# PCB-Main.net
KiCad netlist of a schematic drawn in EAGLE
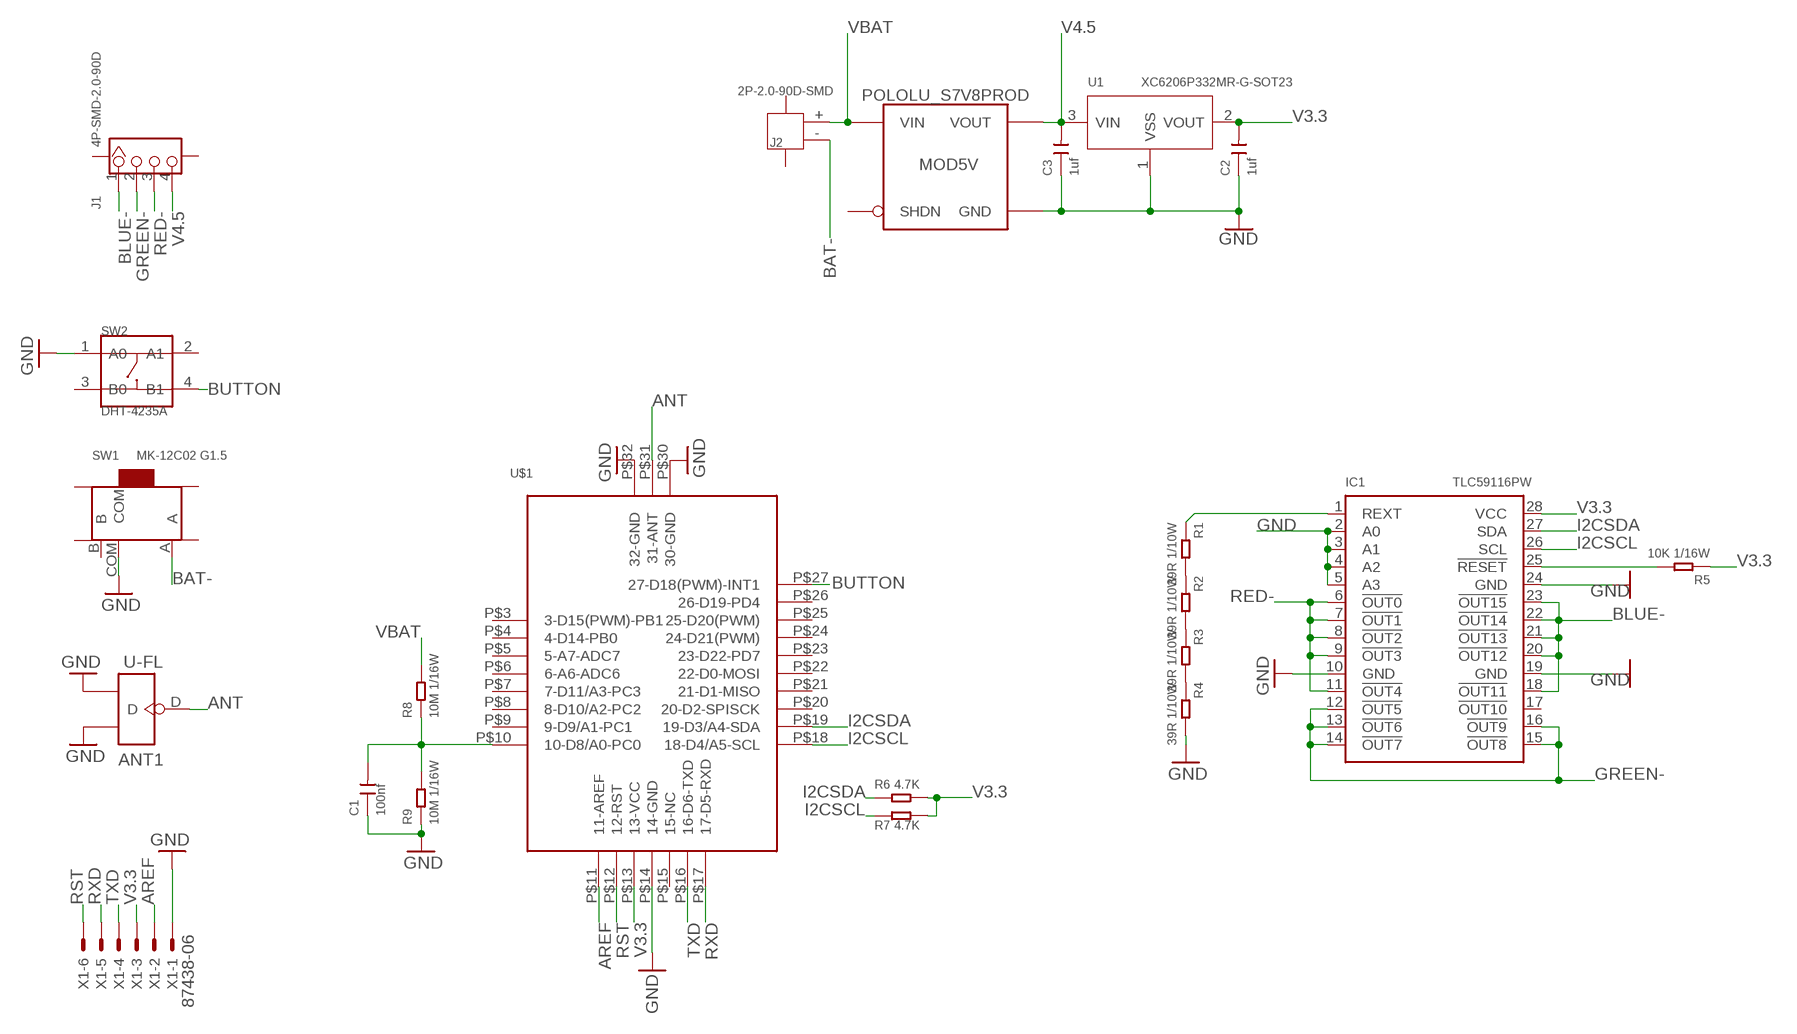
[diagram p0: schematic, sheet 1]

(export (version "E")
  (design (tool "Eeschema 10.0.6"))
  (components
    (comp (ref "ANT1")
      (value "U-FL")
      (footprint "eagle-import:U-FL3P-SMD-2.6X2.6X1.0MM")
      (libsource (lib "eagle-import") (part "ANTENNA-CONN-U-FL(3P)"))
    )
    (comp (ref "C1")
      (value "100nf")
      (footprint "eagle-import:C0402")
      (fields (field (name "MPN") "CC0402KRX7R8BB104"))
      (libsource (lib "eagle-import") (part "CERAMIC-100NF-25V-10%-X7R(0402)"))
    )
    (comp (ref "C2")
      (value "1uf")
      (footprint "eagle-import:C0402")
      (fields (field (name "MPN") "CC0402KRX5R6BB105"))
      (libsource (lib "eagle-import") (part "CERAMIC-1UF-10V-10%-X5R(0402)"))
    )
    (comp (ref "C3")
      (value "1uf")
      (footprint "eagle-import:C0402")
      (fields (field (name "MPN") "CC0402KRX5R6BB105"))
      (libsource (lib "eagle-import") (part "CERAMIC-1UF-10V-10%-X5R(0402)"))
    )
    (comp (ref "IC1")
      (value "TLC59116PW")
      (footprint "eagle-import:PW_R-PDSO-G28")
      (libsource (lib "eagle-import") (part "TLC59116PW"))
    )
    (comp (ref "J1")
      (value "4P-SMD-2.0-90D")
      (footprint "eagle-import:HW4-SMD-2.0-90D")
      (libsource (lib "eagle-import") (part "GROVE-CONNECTOR-SMD-90D(4+2P-2.0)"))
    )
    (comp (ref "J2")
      (value "2P-2.0-90D-SMD")
      (footprint "eagle-import:HW2-SMD-2.0-90D")
      (libsource (lib "eagle-import") (part "CONN-HEADER-SMD-PH-SIDE-(2P-2.0MM)"))
    )
    (comp (ref "MOD5V")
      (value "POLOLU_S7V8PROD")
      (footprint "eagle-import:POLOLU_4P_SIGO")
      (libsource (lib "eagle-import") (part "POLOLU_S7V8PROD"))
    )
    (comp (ref "R1")
      (value "39R 1/10W")
      (footprint "eagle-import:R0603")
      (fields (field (name "MPN") "RC0603JR-0739RL"))
      (libsource (lib "eagle-import") (part "SMD-RES-39R-5%-1/10W(0603)"))
    )
    (comp (ref "R2")
      (value "39R 1/10W")
      (footprint "eagle-import:R0603")
      (fields (field (name "MPN") "RC0603JR-0739RL"))
      (libsource (lib "eagle-import") (part "SMD-RES-39R-5%-1/10W(0603)"))
    )
    (comp (ref "R3")
      (value "39R 1/10W")
      (footprint "eagle-import:R0603")
      (fields (field (name "MPN") "RC0603JR-0739RL"))
      (libsource (lib "eagle-import") (part "SMD-RES-39R-5%-1/10W(0603)"))
    )
    (comp (ref "R4")
      (value "39R 1/10W")
      (footprint "eagle-import:R0603")
      (fields (field (name "MPN") "RC0603JR-0739RL"))
      (libsource (lib "eagle-import") (part "SMD-RES-39R-5%-1/10W(0603)"))
    )
    (comp (ref "R5")
      (value "10K 1/16W")
      (footprint "eagle-import:R0402")
      (fields (field (name "MPN") "RC0402FR-0710KL"))
      (libsource (lib "eagle-import") (part "SMD-RES-10K-1%-1/16W(0402)"))
    )
    (comp (ref "R6")
      (value "4.7K")
      (footprint "eagle-import:R0402")
      (fields (field (name "MPN") "RC0402JR-074K7L"))
      (libsource (lib "eagle-import") (part "SMD-RES-4.7K-5%-1/16W(0402)"))
    )
    (comp (ref "R7")
      (value "4.7K")
      (footprint "eagle-import:R0402")
      (fields (field (name "MPN") "RC0402JR-074K7L"))
      (libsource (lib "eagle-import") (part "SMD-RES-4.7K-5%-1/16W(0402)"))
    )
    (comp (ref "R8")
      (value "10M 1/16W")
      (footprint "eagle-import:R0402")
      (fields (field (name "MPN") "RC0402FR-0710ML"))
      (libsource (lib "eagle-import") (part "SMD-RES-10M-1%-1/16W(0402)"))
    )
    (comp (ref "R9")
      (value "10M 1/16W")
      (footprint "eagle-import:R0402")
      (fields (field (name "MPN") "RC0402FR-0710ML"))
      (libsource (lib "eagle-import") (part "SMD-RES-10M-1%-1/16W(0402)"))
    )
    (comp (ref "SW1")
      (value "MK-12C02 G1.5")
      (footprint "eagle-import:SW7-SMD-L6.7X2.7X3.2MM")
      (libsource (lib "eagle-import") (part "SMD-TOGGLE-SWITCH-ON-ON(3+4P-6.7X2.7MM)"))
    )
    (comp (ref "SW2")
      (value "DHT-4235A")
      (footprint "eagle-import:SW4-SMD-4.2X3.2X2.5MM")
      (libsource (lib "eagle-import") (part "SMD-BUTTON-TOP-DHT-4235A(4P-4.2X3.2MM)"))
    )
    (comp (ref "U$1")
      (value "PANSTAMP-AVR-2")
      (footprint "eagle-import:SMD-PAD-34")
      (libsource (lib "eagle-import") (part "PANSTAMP-AVR-2"))
    )
    (comp (ref "U1")
      (value "XC6206P332MR-G-SOT23")
      (footprint "eagle-import:SOT-23")
      (fields (field (name "MPN") "XC6206P332MR-G"))
      (libsource (lib "eagle-import") (part "PMIC-LDO-XC6206P332MR-G(SOT23)"))
    )
    (comp (ref "X1")
      (value "87438-06")
      (footprint "eagle-import:87438-06")
      (fields (field (name "MPN") "87438-0643"))
      (libsource (lib "eagle-import") (part "87438-06"))
    )
  )
  (nets
    (net (code "1") (name "/ANT") (class "Default")
      (node (ref "ANT1") (pin "D") (pinfunction "D_D") (pintype "bidirectional"))
      (node (ref "U$1") (pin "P$31") (pinfunction "31-ANT_P$31") (pintype "bidirectional"))
    )
    (net (code "2") (name "/AREF") (class "Default")
      (node (ref "U$1") (pin "P$11") (pinfunction "11-AREF_P$11") (pintype "bidirectional"))
      (node (ref "X1") (pin "2") (pinfunction "S_2") (pintype "passive"))
    )
    (net (code "3") (name "/BAT-") (class "Default")
      (node (ref "J2") (pin "-") (pinfunction "2_-") (pintype "bidirectional"))
      (node (ref "SW1") (pin "A") (pinfunction "A_A") (pintype "bidirectional"))
    )
    (net (code "4") (name "/BLUE-") (class "Default")
      (node (ref "IC1") (pin "18") (pinfunction "~{OUT11}_18") (pintype "bidirectional"))
      (node (ref "IC1") (pin "20") (pinfunction "~{OUT12}_20") (pintype "bidirectional"))
      (node (ref "IC1") (pin "21") (pinfunction "~{OUT13}_21") (pintype "bidirectional"))
      (node (ref "IC1") (pin "22") (pinfunction "~{OUT14}_22") (pintype "bidirectional"))
      (node (ref "IC1") (pin "23") (pinfunction "~{OUT15}_23") (pintype "bidirectional"))
      (node (ref "J1") (pin "1") (pinfunction "1_1") (pintype "bidirectional"))
    )
    (net (code "5") (name "/BUTTON") (class "Default")
      (node (ref "SW2") (pin "4") (pinfunction "B1_4") (pintype "bidirectional"))
      (node (ref "U$1") (pin "P$27") (pinfunction "27-D18(PWM)-INT1_P$27") (pintype "bidirectional"))
    )
    (net (code "6") (name "/GREEN-") (class "Default")
      (node (ref "IC1") (pin "12") (pinfunction "~{OUT5}_12") (pintype "bidirectional"))
      (node (ref "IC1") (pin "13") (pinfunction "~{OUT6}_13") (pintype "bidirectional"))
      (node (ref "IC1") (pin "14") (pinfunction "~{OUT7}_14") (pintype "bidirectional"))
      (node (ref "IC1") (pin "15") (pinfunction "~{OUT8}_15") (pintype "bidirectional"))
      (node (ref "IC1") (pin "16") (pinfunction "~{OUT9}_16") (pintype "bidirectional"))
      (node (ref "J1") (pin "2") (pinfunction "2_2") (pintype "bidirectional"))
    )
    (net (code "7") (name "/I2CSCL") (class "Default")
      (node (ref "IC1") (pin "26") (pinfunction "SCL_26") (pintype "bidirectional"))
      (node (ref "R7") (pin "1") (pinfunction "1_1") (pintype "passive"))
      (node (ref "U$1") (pin "P$18") (pinfunction "18-D4/A5-SCL_P$18") (pintype "bidirectional"))
    )
    (net (code "8") (name "/I2CSDA") (class "Default")
      (node (ref "IC1") (pin "27") (pinfunction "SDA_27") (pintype "bidirectional"))
      (node (ref "R6") (pin "1") (pinfunction "1_1") (pintype "passive"))
      (node (ref "U$1") (pin "P$19") (pinfunction "19-D3/A4-SDA_P$19") (pintype "bidirectional"))
    )
    (net (code "9") (name "/RED-") (class "Default")
      (node (ref "IC1") (pin "11") (pinfunction "~{OUT4}_11") (pintype "bidirectional"))
      (node (ref "IC1") (pin "6") (pinfunction "~{OUT0}_6") (pintype "bidirectional"))
      (node (ref "IC1") (pin "7") (pinfunction "~{OUT1}_7") (pintype "bidirectional"))
      (node (ref "IC1") (pin "8") (pinfunction "~{OUT2}_8") (pintype "bidirectional"))
      (node (ref "IC1") (pin "9") (pinfunction "~{OUT3}_9") (pintype "bidirectional"))
      (node (ref "J1") (pin "3") (pinfunction "3_3") (pintype "bidirectional"))
    )
    (net (code "10") (name "/RST") (class "Default")
      (node (ref "U$1") (pin "P$12") (pinfunction "12-RST_P$12") (pintype "bidirectional"))
      (node (ref "X1") (pin "6") (pinfunction "S_6") (pintype "passive"))
    )
    (net (code "11") (name "/RXD") (class "Default")
      (node (ref "U$1") (pin "P$17") (pinfunction "17-D5-RXD_P$17") (pintype "bidirectional"))
      (node (ref "X1") (pin "5") (pinfunction "S_5") (pintype "passive"))
    )
    (net (code "12") (name "/TXD") (class "Default")
      (node (ref "U$1") (pin "P$16") (pinfunction "16-D6-TXD_P$16") (pintype "bidirectional"))
      (node (ref "X1") (pin "4") (pinfunction "S_4") (pintype "passive"))
    )
    (net (code "13") (name "/V3.3") (class "Default")
      (node (ref "C2") (pin "2") (pinfunction "2_2") (pintype "passive"))
      (node (ref "IC1") (pin "28") (pinfunction "VCC_28") (pintype "bidirectional"))
      (node (ref "R5") (pin "1") (pinfunction "1_1") (pintype "passive"))
      (node (ref "R6") (pin "2") (pinfunction "2_2") (pintype "passive"))
      (node (ref "R7") (pin "2") (pinfunction "2_2") (pintype "passive"))
      (node (ref "U$1") (pin "P$13") (pinfunction "13-VCC_P$13") (pintype "bidirectional"))
      (node (ref "U1") (pin "2") (pinfunction "VOUT_2") (pintype "output"))
      (node (ref "X1") (pin "3") (pinfunction "S_3") (pintype "passive"))
    )
    (net (code "14") (name "/V4.5") (class "Default")
      (node (ref "C3") (pin "2") (pinfunction "2_2") (pintype "passive"))
      (node (ref "J1") (pin "4") (pinfunction "4_4") (pintype "bidirectional"))
      (node (ref "MOD5V") (pin "O") (pinfunction "VOUT_O") (pintype "output"))
      (node (ref "U1") (pin "3") (pinfunction "VIN_3") (pintype "input"))
    )
    (net (code "15") (name "/VBAT") (class "Default")
      (node (ref "J2") (pin "+") (pinfunction "1_+") (pintype "bidirectional"))
      (node (ref "MOD5V") (pin "I") (pinfunction "VIN_I") (pintype "power_in"))
      (node (ref "R8") (pin "2") (pinfunction "2_2") (pintype "passive"))
    )
    (net (code "16") (name "GND") (class "Default")
      (node (ref "ANT1") (pin "GND1") (pinfunction "GND1_GND1") (pintype "bidirectional"))
      (node (ref "ANT1") (pin "GND2") (pinfunction "GND2_GND2") (pintype "bidirectional"))
      (node (ref "C1") (pin "1") (pinfunction "1_1") (pintype "passive"))
      (node (ref "C2") (pin "1") (pinfunction "1_1") (pintype "passive"))
      (node (ref "C3") (pin "1") (pinfunction "1_1") (pintype "passive"))
      (node (ref "IC1") (pin "10") (pinfunction "GND_10") (pintype "bidirectional"))
      (node (ref "IC1") (pin "19") (pinfunction "GND_19") (pintype "bidirectional"))
      (node (ref "IC1") (pin "2") (pinfunction "A0_2") (pintype "bidirectional"))
      (node (ref "IC1") (pin "24") (pinfunction "GND_24") (pintype "bidirectional"))
      (node (ref "IC1") (pin "3") (pinfunction "A1_3") (pintype "bidirectional"))
      (node (ref "IC1") (pin "4") (pinfunction "A2_4") (pintype "bidirectional"))
      (node (ref "IC1") (pin "5") (pinfunction "A3_5") (pintype "bidirectional"))
      (node (ref "MOD5V") (pin "G") (pinfunction "GND_G") (pintype "power_in"))
      (node (ref "R4") (pin "2") (pinfunction "2_2") (pintype "passive"))
      (node (ref "R9") (pin "1") (pinfunction "1_1") (pintype "passive"))
      (node (ref "SW1") (pin "COM") (pinfunction "COM_COM") (pintype "bidirectional"))
      (node (ref "SW2") (pin "1") (pinfunction "A0_1") (pintype "bidirectional"))
      (node (ref "U$1") (pin "P$14") (pinfunction "14-GND_P$14") (pintype "bidirectional"))
      (node (ref "U$1") (pin "P$30") (pinfunction "30-GND_P$30") (pintype "bidirectional"))
      (node (ref "U$1") (pin "P$32") (pinfunction "32-GND_P$32") (pintype "bidirectional"))
      (node (ref "U1") (pin "1") (pinfunction "VSS_1") (pintype "power_in"))
      (node (ref "X1") (pin "1") (pinfunction "S_1") (pintype "passive"))
    )
    (net (code "17") (name "Net-(IC1-REXT)") (class "Default")
      (node (ref "IC1") (pin "1") (pinfunction "REXT_1") (pintype "bidirectional"))
      (node (ref "R1") (pin "1") (pinfunction "1_1") (pintype "passive"))
    )
    (net (code "18") (name "Net-(IC1-~{RESET})") (class "Default")
      (node (ref "IC1") (pin "25") (pinfunction "~{RESET}_25") (pintype "bidirectional"))
      (node (ref "R5") (pin "2") (pinfunction "2_2") (pintype "passive"))
    )
    (net (code "19") (name "Net-(R1-Pad2)") (class "Default")
      (node (ref "R1") (pin "2") (pinfunction "2_2") (pintype "passive"))
      (node (ref "R2") (pin "1") (pinfunction "1_1") (pintype "passive"))
    )
    (net (code "20") (name "Net-(R2-Pad2)") (class "Default")
      (node (ref "R2") (pin "2") (pinfunction "2_2") (pintype "passive"))
      (node (ref "R3") (pin "1") (pinfunction "1_1") (pintype "passive"))
    )
    (net (code "21") (name "Net-(R3-Pad2)") (class "Default")
      (node (ref "R3") (pin "2") (pinfunction "2_2") (pintype "passive"))
      (node (ref "R4") (pin "1") (pinfunction "1_1") (pintype "passive"))
    )
    (net (code "22") (name "Net-(U$1-10-D8{slash}A0-PC0)") (class "Default")
      (node (ref "C1") (pin "2") (pinfunction "2_2") (pintype "passive"))
      (node (ref "R8") (pin "1") (pinfunction "1_1") (pintype "passive"))
      (node (ref "R9") (pin "2") (pinfunction "2_2") (pintype "passive"))
      (node (ref "U$1") (pin "P$10") (pinfunction "10-D8/A0-PC0_P$10") (pintype "bidirectional"))
    )
    (net (code "23") (name "unconnected-(IC1-~{OUT10}-Pad17)") (class "Default")
      (node (ref "IC1") (pin "17") (pinfunction "~{OUT10}_17") (pintype "bidirectional"))
    )
    (net (code "24") (name "unconnected-(J1-PadSS1)") (class "Default")
      (node (ref "J1") (pin "SS1") (pinfunction "SS1_SS1") (pintype "bidirectional"))
    )
    (net (code "25") (name "unconnected-(J1-PadSS2)") (class "Default")
      (node (ref "J1") (pin "SS2") (pinfunction "SS2_SS2") (pintype "bidirectional"))
    )
    (net (code "26") (name "unconnected-(J2-Pad3)") (class "Default")
      (node (ref "J2") (pin "3") (pinfunction "3_3") (pintype "bidirectional"))
    )
    (net (code "27") (name "unconnected-(J2-Pad4)") (class "Default")
      (node (ref "J2") (pin "4") (pinfunction "4_4") (pintype "bidirectional"))
    )
    (net (code "28") (name "unconnected-(MOD5V-SHDN-PadS)") (class "Default")
      (node (ref "MOD5V") (pin "S") (pinfunction "SHDN_S") (pintype "input"))
    )
    (net (code "29") (name "unconnected-(SW1-PadB)") (class "Default")
      (node (ref "SW1") (pin "B") (pinfunction "B_B") (pintype "bidirectional"))
    )
    (net (code "30") (name "unconnected-(SW1-PadSS1)") (class "Default")
      (node (ref "SW1") (pin "SS1") (pinfunction "SS1_SS1") (pintype "bidirectional"))
    )
    (net (code "31") (name "unconnected-(SW1-PadSS2)") (class "Default")
      (node (ref "SW1") (pin "SS2") (pinfunction "SS2_SS2") (pintype "bidirectional"))
    )
    (net (code "32") (name "unconnected-(SW1-PadSS3)") (class "Default")
      (node (ref "SW1") (pin "SS3") (pinfunction "SS3_SS3") (pintype "bidirectional"))
    )
    (net (code "33") (name "unconnected-(SW1-PadSS4)") (class "Default")
      (node (ref "SW1") (pin "SS4") (pinfunction "SS4_SS4") (pintype "bidirectional"))
    )
    (net (code "34") (name "unconnected-(SW2-A1-Pad2)") (class "Default")
      (node (ref "SW2") (pin "2") (pinfunction "A1_2") (pintype "bidirectional"))
    )
    (net (code "35") (name "unconnected-(SW2-B0-Pad3)") (class "Default")
      (node (ref "SW2") (pin "3") (pinfunction "B0_3") (pintype "bidirectional"))
    )
    (net (code "36") (name "unconnected-(U$1-3-D15(PWM)-PB1-PadP$3)") (class "Default")
      (node (ref "U$1") (pin "P$3") (pinfunction "3-D15(PWM)-PB1_P$3") (pintype "bidirectional"))
    )
    (net (code "37") (name "unconnected-(U$1-4-D14-PB0-PadP$4)") (class "Default")
      (node (ref "U$1") (pin "P$4") (pinfunction "4-D14-PB0_P$4") (pintype "bidirectional"))
    )
    (net (code "38") (name "unconnected-(U$1-5-A7-ADC7-PadP$5)") (class "Default")
      (node (ref "U$1") (pin "P$5") (pinfunction "5-A7-ADC7_P$5") (pintype "bidirectional"))
    )
    (net (code "39") (name "unconnected-(U$1-6-A6-ADC6-PadP$6)") (class "Default")
      (node (ref "U$1") (pin "P$6") (pinfunction "6-A6-ADC6_P$6") (pintype "bidirectional"))
    )
    (net (code "40") (name "unconnected-(U$1-7-D11{slash}A3-PC3-PadP$7)") (class "Default")
      (node (ref "U$1") (pin "P$7") (pinfunction "7-D11/A3-PC3_P$7") (pintype "bidirectional"))
    )
    (net (code "41") (name "unconnected-(U$1-8-D10{slash}A2-PC2-PadP$8)") (class "Default")
      (node (ref "U$1") (pin "P$8") (pinfunction "8-D10/A2-PC2_P$8") (pintype "bidirectional"))
    )
    (net (code "42") (name "unconnected-(U$1-9-D9{slash}A1-PC1-PadP$9)") (class "Default")
      (node (ref "U$1") (pin "P$9") (pinfunction "9-D9/A1-PC1_P$9") (pintype "bidirectional"))
    )
    (net (code "43") (name "unconnected-(U$1-15-NC-PadP$15)") (class "Default")
      (node (ref "U$1") (pin "P$15") (pinfunction "15-NC_P$15") (pintype "bidirectional"))
    )
    (net (code "44") (name "unconnected-(U$1-20-D2-SPISCK-PadP$20)") (class "Default")
      (node (ref "U$1") (pin "P$20") (pinfunction "20-D2-SPISCK_P$20") (pintype "bidirectional"))
    )
    (net (code "45") (name "unconnected-(U$1-21-D1-MISO-PadP$21)") (class "Default")
      (node (ref "U$1") (pin "P$21") (pinfunction "21-D1-MISO_P$21") (pintype "bidirectional"))
    )
    (net (code "46") (name "unconnected-(U$1-22-D0-MOSI-PadP$22)") (class "Default")
      (node (ref "U$1") (pin "P$22") (pinfunction "22-D0-MOSI_P$22") (pintype "bidirectional"))
    )
    (net (code "47") (name "unconnected-(U$1-23-D22-PD7-PadP$23)") (class "Default")
      (node (ref "U$1") (pin "P$23") (pinfunction "23-D22-PD7_P$23") (pintype "bidirectional"))
    )
    (net (code "48") (name "unconnected-(U$1-24-D21(PWM)-PadP$24)") (class "Default")
      (node (ref "U$1") (pin "P$24") (pinfunction "24-D21(PWM)_P$24") (pintype "bidirectional"))
    )
    (net (code "49") (name "unconnected-(U$1-25-D20(PWM)-PadP$25)") (class "Default")
      (node (ref "U$1") (pin "P$25") (pinfunction "25-D20(PWM)_P$25") (pintype "bidirectional"))
    )
    (net (code "50") (name "unconnected-(U$1-26-D19-PD4-PadP$26)") (class "Default")
      (node (ref "U$1") (pin "P$26") (pinfunction "26-D19-PD4_P$26") (pintype "bidirectional"))
    )
  )
)
